# pass_through_adaptor_1_1.net
KiCad netlist of a schematic drawn in EAGLE
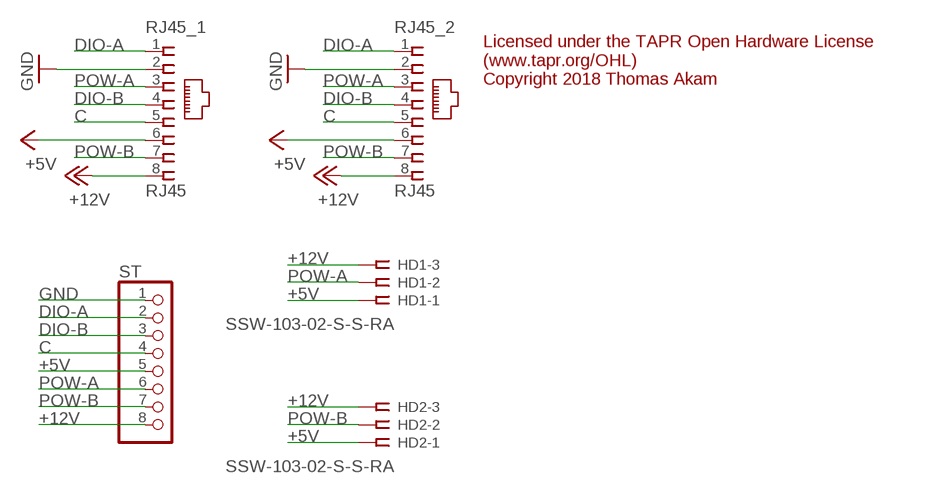
[diagram p0: schematic, sheet 1]

(export (version "E")
  (design (tool "Eeschema 10.0.6"))
  (components
    (comp (ref "HD1")
      (value "SSW-103-02-S-S-RA")
      (footprint "eagle-import:SSW-103-02-S-S-RA")
      (libsource (lib "eagle-import") (part "SSW-103-02-S-S-RA"))
    )
    (comp (ref "HD2")
      (value "SSW-103-02-S-S-RA")
      (footprint "eagle-import:SSW-103-02-S-S-RA")
      (libsource (lib "eagle-import") (part "SSW-103-02-S-S-RA"))
    )
    (comp (ref "RJ45_1")
      (value "RJ45")
      (footprint "eagle-import:RJ45-NO-SHIELD-VERTICAL")
      (libsource (lib "eagle-import") (part "RJ45VERTICAL"))
    )
    (comp (ref "RJ45_2")
      (value "RJ45")
      (footprint "eagle-import:RJ45-NO-SHIELD-VERTICAL")
      (libsource (lib "eagle-import") (part "RJ45VERTICAL"))
    )
    (comp (ref "ST")
      (value "PINHD-1X8")
      (footprint "eagle-import:1X08")
      (libsource (lib "eagle-import") (part "PINHD-1X8"))
    )
  )
  (nets
    (net (code "1") (name "+5V") (class "Default")
      (node (ref "HD1") (pin "1") (pinfunction "1_1") (pintype "passive"))
      (node (ref "HD2") (pin "1") (pinfunction "1_1") (pintype "passive"))
      (node (ref "RJ45_1") (pin "6") (pinfunction "6_6") (pintype "passive"))
      (node (ref "RJ45_2") (pin "6") (pinfunction "6_6") (pintype "passive"))
      (node (ref "ST") (pin "5") (pinfunction "5_5") (pintype "passive"))
    )
    (net (code "2") (name "+12V") (class "Default")
      (node (ref "HD1") (pin "3") (pinfunction "1_3") (pintype "passive"))
      (node (ref "HD2") (pin "3") (pinfunction "1_3") (pintype "passive"))
      (node (ref "RJ45_1") (pin "8") (pinfunction "8_8") (pintype "passive"))
      (node (ref "RJ45_2") (pin "8") (pinfunction "8_8") (pintype "passive"))
      (node (ref "ST") (pin "8") (pinfunction "8_8") (pintype "passive"))
    )
    (net (code "3") (name "/C") (class "Default")
      (node (ref "RJ45_1") (pin "5") (pinfunction "5_5") (pintype "passive"))
      (node (ref "RJ45_2") (pin "5") (pinfunction "5_5") (pintype "passive"))
      (node (ref "ST") (pin "4") (pinfunction "4_4") (pintype "passive"))
    )
    (net (code "4") (name "/DIO-A") (class "Default")
      (node (ref "RJ45_1") (pin "1") (pinfunction "1_1") (pintype "passive"))
      (node (ref "RJ45_2") (pin "1") (pinfunction "1_1") (pintype "passive"))
      (node (ref "ST") (pin "2") (pinfunction "2_2") (pintype "passive"))
    )
    (net (code "5") (name "/DIO-B") (class "Default")
      (node (ref "RJ45_1") (pin "4") (pinfunction "4_4") (pintype "passive"))
      (node (ref "RJ45_2") (pin "4") (pinfunction "4_4") (pintype "passive"))
      (node (ref "ST") (pin "3") (pinfunction "3_3") (pintype "passive"))
    )
    (net (code "6") (name "/POW-A") (class "Default")
      (node (ref "HD1") (pin "2") (pinfunction "1_2") (pintype "passive"))
      (node (ref "RJ45_1") (pin "3") (pinfunction "3_3") (pintype "passive"))
      (node (ref "RJ45_2") (pin "3") (pinfunction "3_3") (pintype "passive"))
      (node (ref "ST") (pin "6") (pinfunction "6_6") (pintype "passive"))
    )
    (net (code "7") (name "/POW-B") (class "Default")
      (node (ref "HD2") (pin "2") (pinfunction "1_2") (pintype "passive"))
      (node (ref "RJ45_1") (pin "7") (pinfunction "7_7") (pintype "passive"))
      (node (ref "RJ45_2") (pin "7") (pinfunction "7_7") (pintype "passive"))
      (node (ref "ST") (pin "7") (pinfunction "7_7") (pintype "passive"))
    )
    (net (code "8") (name "GND") (class "Default")
      (node (ref "RJ45_1") (pin "2") (pinfunction "2_2") (pintype "passive"))
      (node (ref "RJ45_2") (pin "2") (pinfunction "2_2") (pintype "passive"))
      (node (ref "ST") (pin "1") (pinfunction "1_1") (pintype "passive"))
    )
  )
)
